# pi_shield_R4.net
KiCad netlist of a schematic drawn in EAGLE
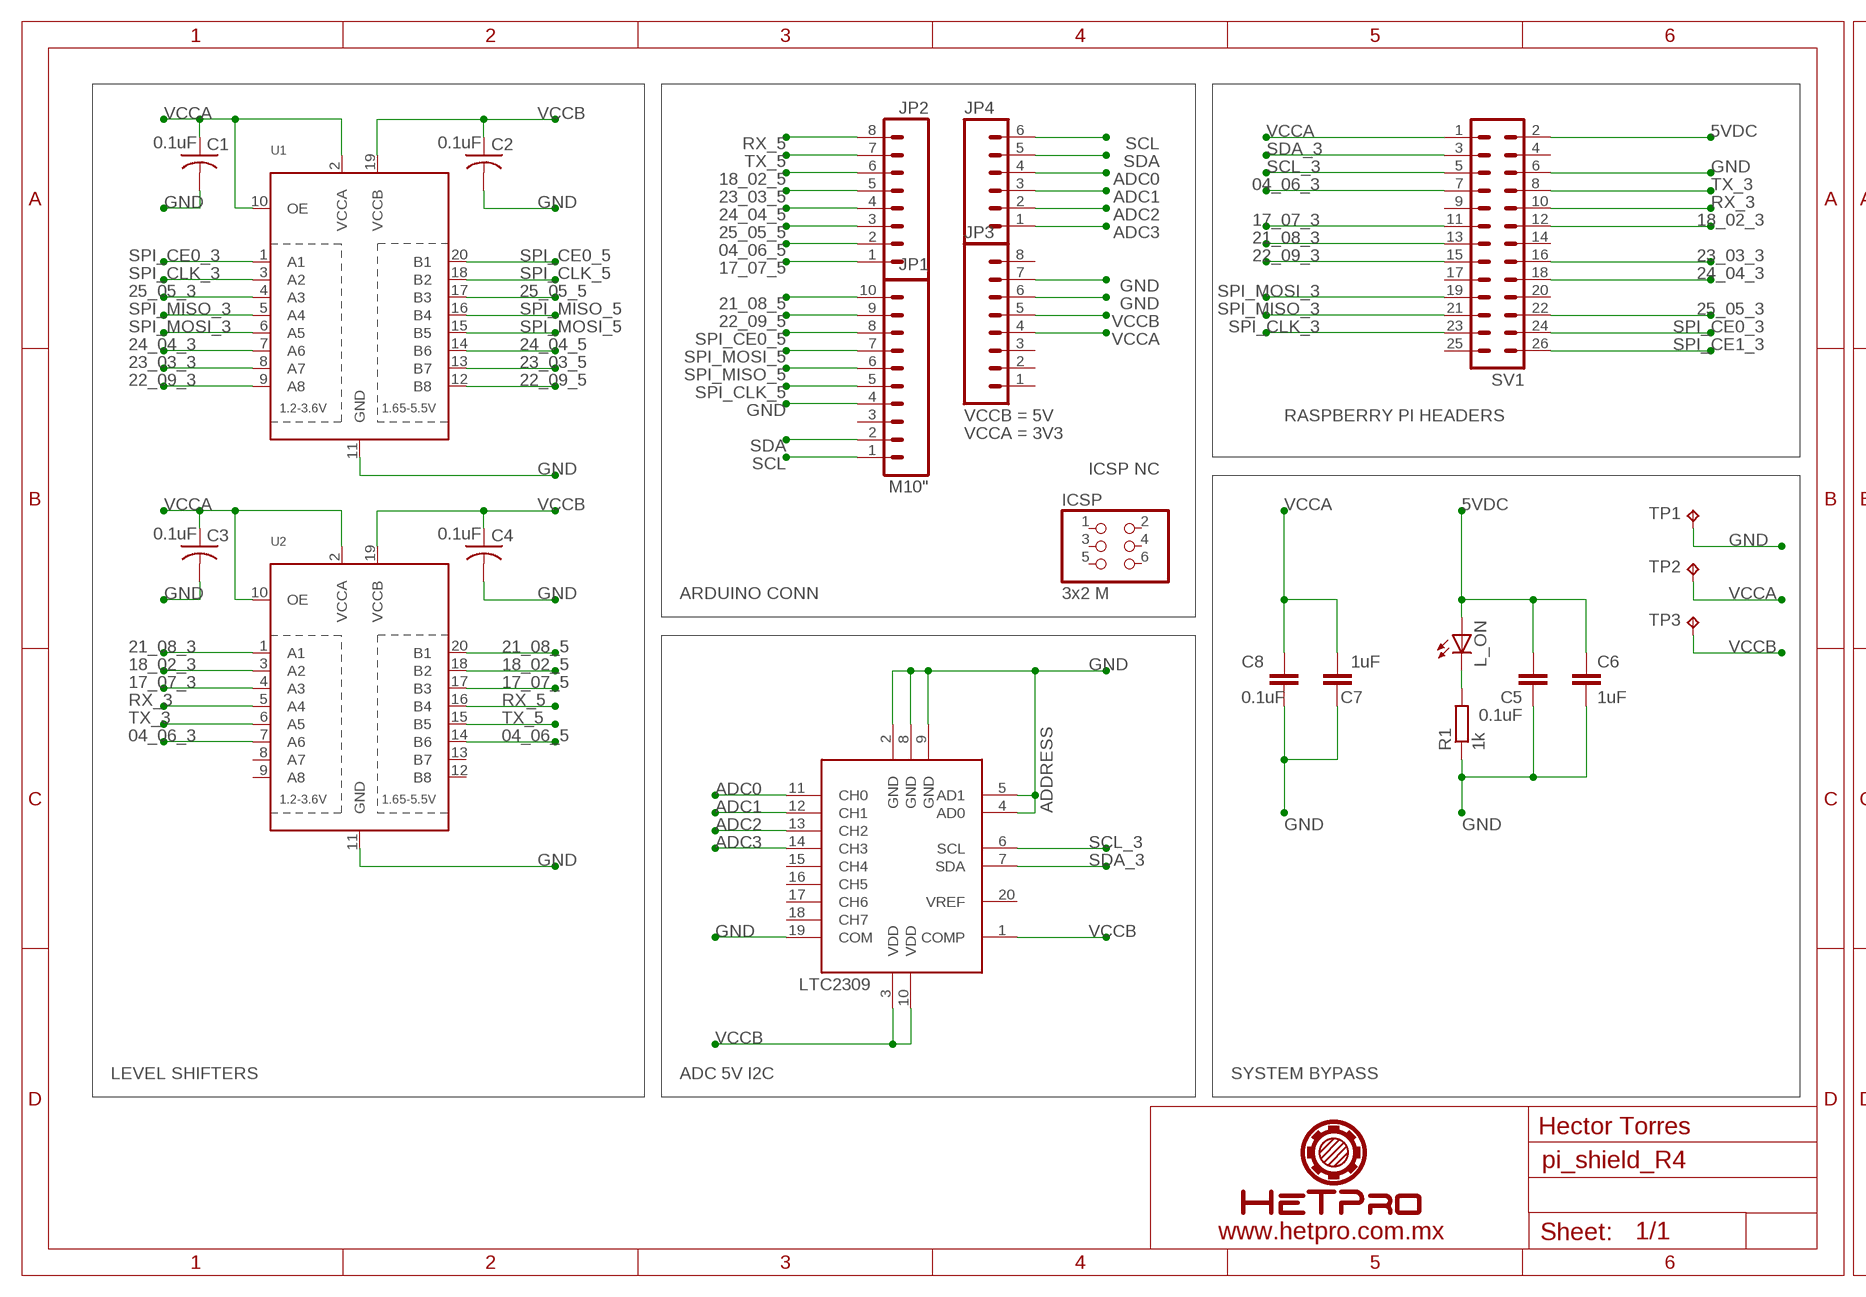
[diagram p0: schematic, sheet 1, part 1 of 2]
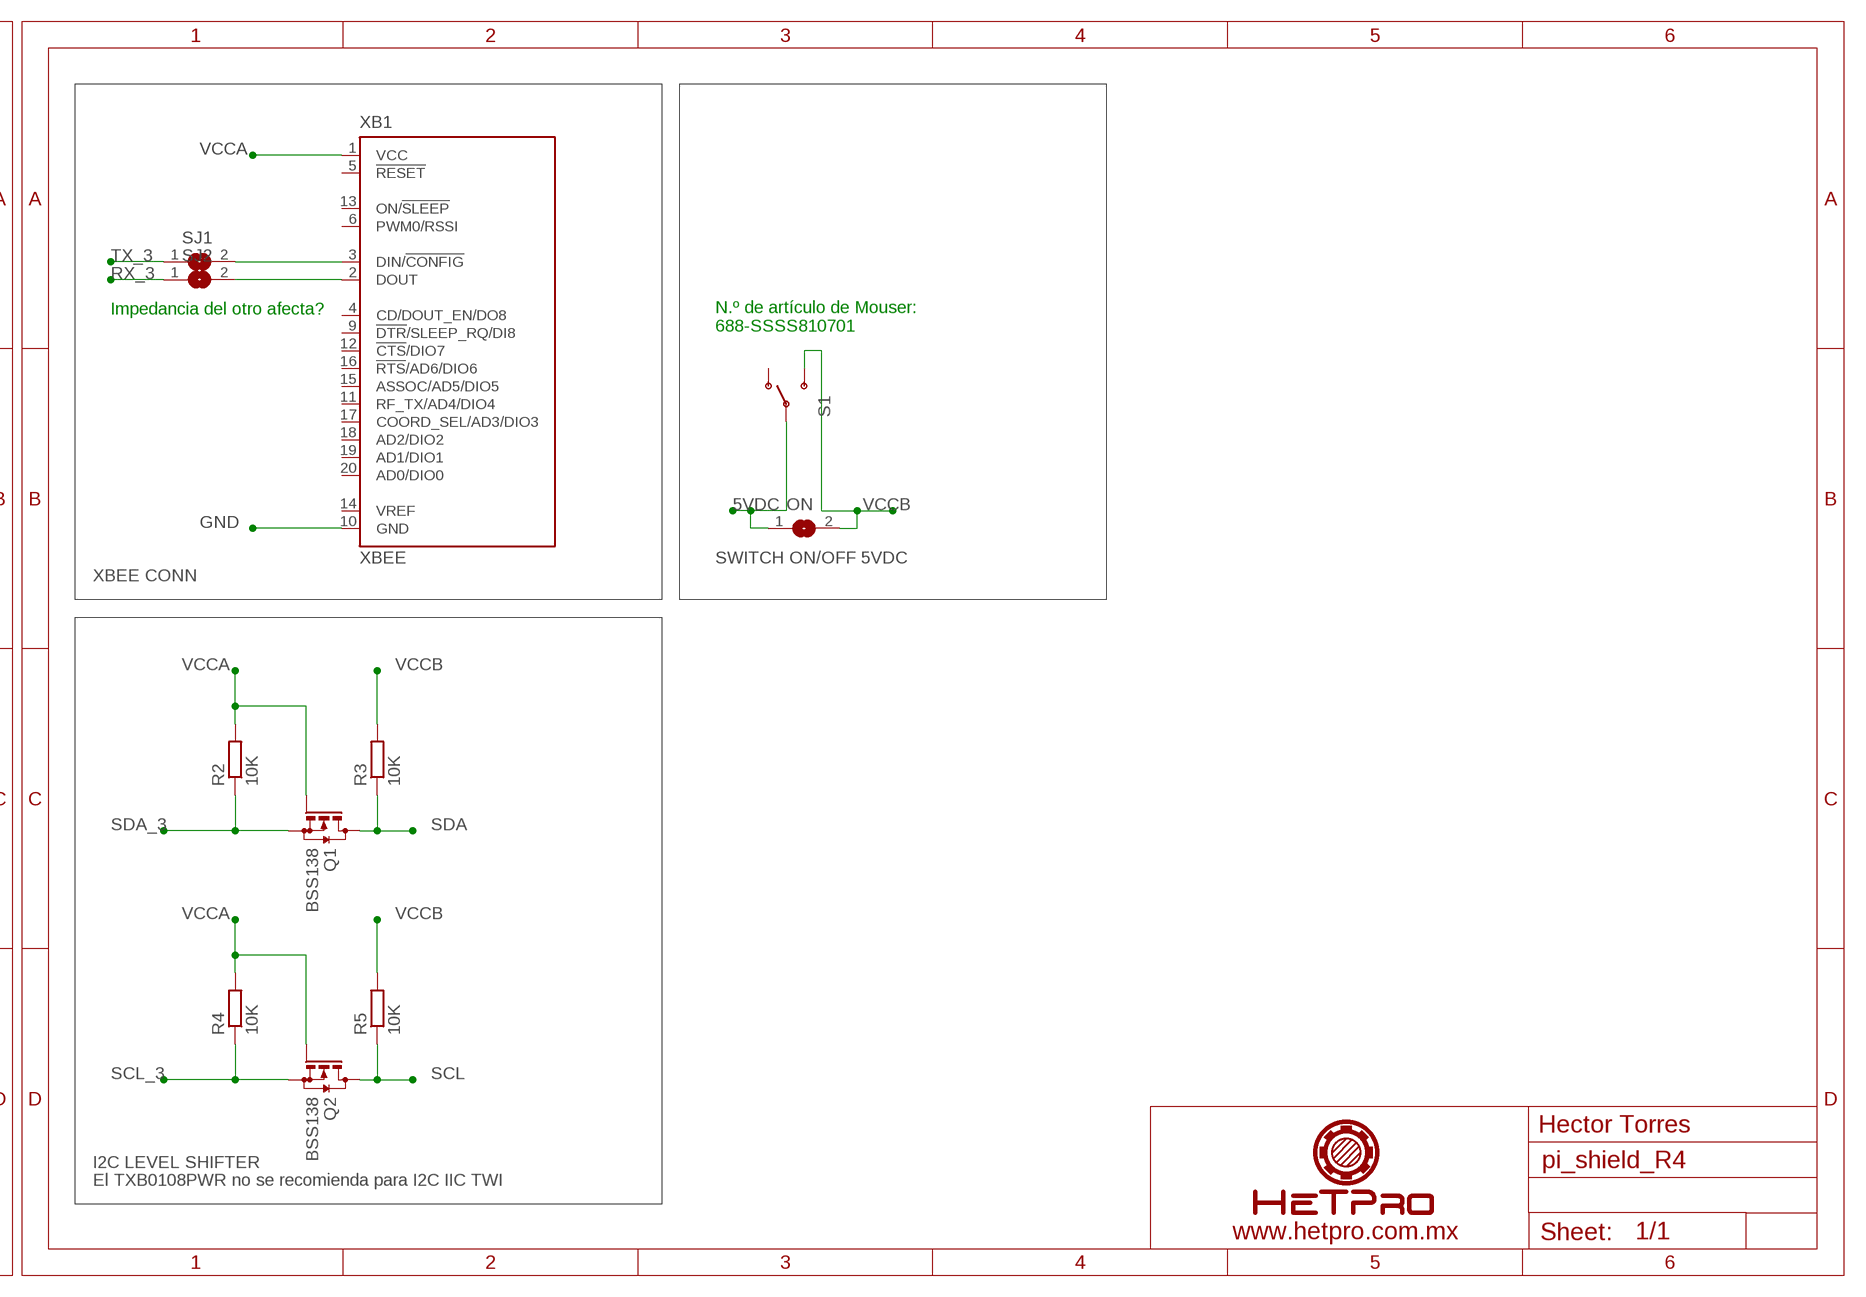
[diagram p1: schematic, sheet 1, part 2 of 2]

(export (version "E")
  (design (tool "Eeschema 10.0.6"))
  (components
    (comp (ref "C1")
      (value "0.1uF")
      (footprint "eagle-import:C0603")
      (libsource (lib "eagle-import") (part "C-USC0603"))
    )
    (comp (ref "C2")
      (value "0.1uF")
      (footprint "eagle-import:C0603")
      (libsource (lib "eagle-import") (part "C-USC0603"))
    )
    (comp (ref "C3")
      (value "0.1uF")
      (footprint "eagle-import:C0603")
      (libsource (lib "eagle-import") (part "C-USC0603"))
    )
    (comp (ref "C4")
      (value "0.1uF")
      (footprint "eagle-import:C0603")
      (libsource (lib "eagle-import") (part "C-USC0603"))
    )
    (comp (ref "C5")
      (value "0.1uF")
      (footprint "eagle-import:C0603")
      (libsource (lib "eagle-import") (part "C-EUC0603"))
    )
    (comp (ref "C6")
      (value "1uF")
      (footprint "eagle-import:C1206")
      (libsource (lib "eagle-import") (part "C-EUC1206"))
    )
    (comp (ref "C7")
      (value "1uF")
      (footprint "eagle-import:C0603")
      (libsource (lib "eagle-import") (part "C-EUC0603"))
    )
    (comp (ref "C8")
      (value "0.1uF")
      (footprint "eagle-import:C1206")
      (libsource (lib "eagle-import") (part "C-EUC1206"))
    )
    (comp (ref "ICSP")
      (value "3x2 M")
      (footprint "eagle-import:2X03")
      (libsource (lib "eagle-import") (part "PINHD-2X3"))
    )
    (comp (ref "JP1")
      (value "M10\"")
      (footprint "eagle-import:1X10")
      (libsource (lib "eagle-import") (part "M10{dblquote}"))
    )
    (comp (ref "JP2")
      (value "M081X08")
      (footprint "eagle-import:1X08")
      (libsource (lib "eagle-import") (part "M081X08"))
    )
    (comp (ref "JP3")
      (value "M081X08")
      (footprint "eagle-import:1X08")
      (libsource (lib "eagle-import") (part "M081X08"))
    )
    (comp (ref "JP4")
      (value "M06SIP")
      (footprint "eagle-import:1X06")
      (libsource (lib "eagle-import") (part "M06SIP"))
    )
    (comp (ref "L_ON")
      (value "LEDCHIPLED_1206")
      (footprint "eagle-import:CHIPLED_1206")
      (libsource (lib "eagle-import") (part "LEDCHIPLED_1206"))
    )
    (comp (ref "ON") (value "SJ") (footprint "eagle-import:SJ") (libsource (lib "eagle-import") (part "SJ")))
    (comp (ref "Q1")
      (value "BSS138")
      (footprint "eagle-import:SOT23")
      (libsource (lib "eagle-import") (part "BSS123"))
    )
    (comp (ref "Q2")
      (value "BSS138")
      (footprint "eagle-import:SOT23")
      (libsource (lib "eagle-import") (part "BSS123"))
    )
    (comp (ref "R1")
      (value "1k")
      (footprint "eagle-import:R0603")
      (libsource (lib "eagle-import") (part "R-EU_R0603"))
    )
    (comp (ref "R2")
      (value "10K")
      (footprint "eagle-import:R0603")
      (libsource (lib "eagle-import") (part "R-EU_R0603"))
    )
    (comp (ref "R3")
      (value "10K")
      (footprint "eagle-import:R0603")
      (libsource (lib "eagle-import") (part "R-EU_R0603"))
    )
    (comp (ref "R4")
      (value "10K")
      (footprint "eagle-import:R0603")
      (libsource (lib "eagle-import") (part "R-EU_R0603"))
    )
    (comp (ref "R5")
      (value "10K")
      (footprint "eagle-import:R0603")
      (libsource (lib "eagle-import") (part "R-EU_R0603"))
    )
    (comp (ref "S1")
      (value "SWITCH-SPST-SMD-A")
      (footprint "eagle-import:SWITCH-SPST-SMD-A")
      (libsource (lib "eagle-import") (part "SWITCH-SPST-SMD-A"))
    )
    (comp (ref "SJ1") (value "SJ") (footprint "eagle-import:SJ") (libsource (lib "eagle-import") (part "SJ")))
    (comp (ref "SJ2") (value "SJ") (footprint "eagle-import:SJ") (libsource (lib "eagle-import") (part "SJ")))
    (comp (ref "SV1")
      (value "MA13-2")
      (footprint "eagle-import:MA13-2")
      (fields (field (name "OC_FARNELL") "unknown") (field (name "OC_NEWARK") "unknown"))
      (libsource (lib "eagle-import") (part "MA13-2"))
    )
    (comp (ref "TP1")
      (value "TPTP20SQ")
      (footprint "eagle-import:TP20SQ")
      (libsource (lib "eagle-import") (part "TPTP20SQ"))
    )
    (comp (ref "TP2")
      (value "TPTP20SQ")
      (footprint "eagle-import:TP20SQ")
      (libsource (lib "eagle-import") (part "TPTP20SQ"))
    )
    (comp (ref "TP3")
      (value "TPTP20SQ")
      (footprint "eagle-import:TP20SQ")
      (libsource (lib "eagle-import") (part "TPTP20SQ"))
    )
    (comp (ref "U$4")
      (value "LTC2309")
      (footprint "eagle-import:TSSOP20")
      (libsource (lib "eagle-import") (part "LTC2309_TSSOP20"))
    )
    (comp (ref "U1")
      (value "TXB0108PWR")
      (footprint "eagle-import:TSSOP20")
      (libsource (lib "eagle-import") (part "TXB0108PWR"))
    )
    (comp (ref "U2")
      (value "TXB0108PWR")
      (footprint "eagle-import:TSSOP20")
      (libsource (lib "eagle-import") (part "TXB0108PWR"))
    )
    (comp (ref "XB1")
      (value "XBEE")
      (footprint "eagle-import:XBEE")
      (fields (field (name "MPN") "XBP24-Z7UIT-004"))
      (libsource (lib "eagle-import") (part "XBEE"))
    )
  )
  (nets
    (net (code "1") (name "/04_06_3") (class "Default")
      (node (ref "SV1") (pin "7") (pinfunction "7_7") (pintype "passive"))
      (node (ref "U2") (pin "7") (pinfunction "A6_7") (pintype "bidirectional"))
    )
    (net (code "2") (name "/04_06_5") (class "Default")
      (node (ref "JP2") (pin "2") (pinfunction "2_2") (pintype "passive"))
      (node (ref "U2") (pin "14") (pinfunction "B6_14") (pintype "bidirectional"))
    )
    (net (code "3") (name "/5VDC") (class "Default")
      (node (ref "C5") (pin "2") (pinfunction "2_2") (pintype "passive"))
      (node (ref "C6") (pin "1") (pinfunction "1_1") (pintype "passive"))
      (node (ref "L_ON") (pin "A") (pinfunction "A_A") (pintype "passive"))
      (node (ref "ON") (pin "1") (pinfunction "1_1") (pintype "passive"))
      (node (ref "S1") (pin "2") (pinfunction "P_2") (pintype "passive"))
      (node (ref "SV1") (pin "2") (pinfunction "2_2") (pintype "passive"))
    )
    (net (code "4") (name "/17_07_3") (class "Default")
      (node (ref "SV1") (pin "11") (pinfunction "11_11") (pintype "passive"))
      (node (ref "U2") (pin "4") (pinfunction "A3_4") (pintype "bidirectional"))
    )
    (net (code "5") (name "/17_07_5") (class "Default")
      (node (ref "JP2") (pin "1") (pinfunction "1_1") (pintype "passive"))
      (node (ref "U2") (pin "17") (pinfunction "B3_17") (pintype "bidirectional"))
    )
    (net (code "6") (name "/18_02_3") (class "Default")
      (node (ref "SV1") (pin "12") (pinfunction "12_12") (pintype "passive"))
      (node (ref "U2") (pin "3") (pinfunction "A2_3") (pintype "bidirectional"))
    )
    (net (code "7") (name "/18_02_5") (class "Default")
      (node (ref "JP2") (pin "6") (pinfunction "6_6") (pintype "passive"))
      (node (ref "U2") (pin "18") (pinfunction "B2_18") (pintype "bidirectional"))
    )
    (net (code "8") (name "/21_08_3") (class "Default")
      (node (ref "SV1") (pin "13") (pinfunction "13_13") (pintype "passive"))
      (node (ref "U2") (pin "1") (pinfunction "A1_1") (pintype "bidirectional"))
    )
    (net (code "9") (name "/21_08_5") (class "Default")
      (node (ref "JP1") (pin "10") (pinfunction "10_10") (pintype "passive"))
      (node (ref "U2") (pin "20") (pinfunction "B1_20") (pintype "bidirectional"))
    )
    (net (code "10") (name "/22_09_3") (class "Default")
      (node (ref "SV1") (pin "15") (pinfunction "15_15") (pintype "passive"))
      (node (ref "U1") (pin "9") (pinfunction "A8_9") (pintype "bidirectional"))
    )
    (net (code "11") (name "/22_09_5") (class "Default")
      (node (ref "JP1") (pin "9") (pinfunction "9_9") (pintype "passive"))
      (node (ref "U1") (pin "12") (pinfunction "B8_12") (pintype "bidirectional"))
    )
    (net (code "12") (name "/23_03_3") (class "Default")
      (node (ref "SV1") (pin "16") (pinfunction "16_16") (pintype "passive"))
      (node (ref "U1") (pin "8") (pinfunction "A7_8") (pintype "bidirectional"))
    )
    (net (code "13") (name "/23_03_5") (class "Default")
      (node (ref "JP2") (pin "5") (pinfunction "5_5") (pintype "passive"))
      (node (ref "U1") (pin "13") (pinfunction "B7_13") (pintype "bidirectional"))
    )
    (net (code "14") (name "/24_04_3") (class "Default")
      (node (ref "SV1") (pin "18") (pinfunction "18_18") (pintype "passive"))
      (node (ref "U1") (pin "7") (pinfunction "A6_7") (pintype "bidirectional"))
    )
    (net (code "15") (name "/24_04_5") (class "Default")
      (node (ref "JP2") (pin "4") (pinfunction "4_4") (pintype "passive"))
      (node (ref "U1") (pin "14") (pinfunction "B6_14") (pintype "bidirectional"))
    )
    (net (code "16") (name "/25_05_3") (class "Default")
      (node (ref "SV1") (pin "22") (pinfunction "22_22") (pintype "passive"))
      (node (ref "U1") (pin "4") (pinfunction "A3_4") (pintype "bidirectional"))
    )
    (net (code "17") (name "/25_05_5") (class "Default")
      (node (ref "JP2") (pin "3") (pinfunction "3_3") (pintype "passive"))
      (node (ref "U1") (pin "17") (pinfunction "B3_17") (pintype "bidirectional"))
    )
    (net (code "18") (name "/ADC0") (class "Default")
      (node (ref "JP4") (pin "4") (pinfunction "4_4") (pintype "passive"))
      (node (ref "U$4") (pin "11") (pinfunction "CH0_11") (pintype "bidirectional"))
    )
    (net (code "19") (name "/ADC1") (class "Default")
      (node (ref "JP4") (pin "3") (pinfunction "3_3") (pintype "passive"))
      (node (ref "U$4") (pin "12") (pinfunction "CH1_12") (pintype "bidirectional"))
    )
    (net (code "20") (name "/ADC2") (class "Default")
      (node (ref "JP4") (pin "2") (pinfunction "2_2") (pintype "passive"))
      (node (ref "U$4") (pin "13") (pinfunction "CH2_13") (pintype "bidirectional"))
    )
    (net (code "21") (name "/ADC3") (class "Default")
      (node (ref "JP4") (pin "1") (pinfunction "1_1") (pintype "passive"))
      (node (ref "U$4") (pin "14") (pinfunction "CH3_14") (pintype "bidirectional"))
    )
    (net (code "22") (name "/GND") (class "Default")
      (node (ref "C1") (pin "2") (pinfunction "2_2") (pintype "passive"))
      (node (ref "C2") (pin "2") (pinfunction "2_2") (pintype "passive"))
      (node (ref "C3") (pin "2") (pinfunction "2_2") (pintype "passive"))
      (node (ref "C4") (pin "2") (pinfunction "2_2") (pintype "passive"))
      (node (ref "C5") (pin "1") (pinfunction "1_1") (pintype "passive"))
      (node (ref "C6") (pin "2") (pinfunction "2_2") (pintype "passive"))
      (node (ref "C7") (pin "1") (pinfunction "1_1") (pintype "passive"))
      (node (ref "C8") (pin "2") (pinfunction "2_2") (pintype "passive"))
      (node (ref "JP1") (pin "4") (pinfunction "4_4") (pintype "passive"))
      (node (ref "JP3") (pin "6") (pinfunction "6_6") (pintype "passive"))
      (node (ref "JP3") (pin "7") (pinfunction "7_7") (pintype "passive"))
      (node (ref "R1") (pin "1") (pinfunction "1_1") (pintype "passive"))
      (node (ref "SV1") (pin "6") (pinfunction "6_6") (pintype "passive"))
      (node (ref "TP1") (pin "TP") (pinfunction "TP_TP") (pintype "input"))
      (node (ref "U$4") (pin "19") (pinfunction "COM_19") (pintype "bidirectional"))
      (node (ref "U$4") (pin "2") (pinfunction "GND_2") (pintype "bidirectional"))
      (node (ref "U$4") (pin "4") (pinfunction "AD0_4") (pintype "bidirectional"))
      (node (ref "U$4") (pin "5") (pinfunction "AD1_5") (pintype "bidirectional"))
      (node (ref "U$4") (pin "8") (pinfunction "GND_8") (pintype "bidirectional"))
      (node (ref "U$4") (pin "9") (pinfunction "GND_9") (pintype "bidirectional"))
      (node (ref "U1") (pin "11") (pinfunction "GND_11") (pintype "bidirectional"))
      (node (ref "U2") (pin "11") (pinfunction "GND_11") (pintype "bidirectional"))
      (node (ref "XB1") (pin "10") (pinfunction "GND_10") (pintype "power_in"))
    )
    (net (code "23") (name "/RX_3") (class "Default")
      (node (ref "SJ2") (pin "1") (pinfunction "1_1") (pintype "passive"))
      (node (ref "SV1") (pin "10") (pinfunction "10_10") (pintype "passive"))
      (node (ref "U2") (pin "5") (pinfunction "A4_5") (pintype "bidirectional"))
    )
    (net (code "24") (name "/RX_5") (class "Default")
      (node (ref "JP2") (pin "8") (pinfunction "8_8") (pintype "passive"))
      (node (ref "U2") (pin "16") (pinfunction "B4_16") (pintype "bidirectional"))
    )
    (net (code "25") (name "/SCL") (class "Default")
      (node (ref "JP1") (pin "1") (pinfunction "1_1") (pintype "passive"))
      (node (ref "JP4") (pin "6") (pinfunction "6_6") (pintype "passive"))
      (node (ref "Q2") (pin "3") (pinfunction "D_3") (pintype "passive"))
      (node (ref "R5") (pin "1") (pinfunction "1_1") (pintype "passive"))
    )
    (net (code "26") (name "/SCL_3") (class "Default")
      (node (ref "Q2") (pin "2") (pinfunction "S_2") (pintype "passive"))
      (node (ref "R4") (pin "1") (pinfunction "1_1") (pintype "passive"))
      (node (ref "SV1") (pin "5") (pinfunction "5_5") (pintype "passive"))
      (node (ref "U$4") (pin "6") (pinfunction "SCL_6") (pintype "bidirectional"))
    )
    (net (code "27") (name "/SDA") (class "Default")
      (node (ref "JP1") (pin "2") (pinfunction "2_2") (pintype "passive"))
      (node (ref "JP4") (pin "5") (pinfunction "5_5") (pintype "passive"))
      (node (ref "Q1") (pin "3") (pinfunction "D_3") (pintype "passive"))
      (node (ref "R3") (pin "1") (pinfunction "1_1") (pintype "passive"))
    )
    (net (code "28") (name "/SDA_3") (class "Default")
      (node (ref "Q1") (pin "2") (pinfunction "S_2") (pintype "passive"))
      (node (ref "R2") (pin "1") (pinfunction "1_1") (pintype "passive"))
      (node (ref "SV1") (pin "3") (pinfunction "3_3") (pintype "passive"))
      (node (ref "U$4") (pin "7") (pinfunction "SDA_7") (pintype "bidirectional"))
    )
    (net (code "29") (name "/SPI_CE0_3") (class "Default")
      (node (ref "SV1") (pin "24") (pinfunction "24_24") (pintype "passive"))
      (node (ref "U1") (pin "1") (pinfunction "A1_1") (pintype "bidirectional"))
    )
    (net (code "30") (name "/SPI_CE0_5") (class "Default")
      (node (ref "JP1") (pin "8") (pinfunction "8_8") (pintype "passive"))
      (node (ref "U1") (pin "20") (pinfunction "B1_20") (pintype "bidirectional"))
    )
    (net (code "31") (name "/SPI_CE1_3") (class "Default")
      (node (ref "SV1") (pin "26") (pinfunction "26_26") (pintype "passive"))
    )
    (net (code "32") (name "/SPI_CLK_3") (class "Default")
      (node (ref "SV1") (pin "23") (pinfunction "23_23") (pintype "passive"))
      (node (ref "U1") (pin "3") (pinfunction "A2_3") (pintype "bidirectional"))
    )
    (net (code "33") (name "/SPI_CLK_5") (class "Default")
      (node (ref "JP1") (pin "5") (pinfunction "5_5") (pintype "passive"))
      (node (ref "U1") (pin "18") (pinfunction "B2_18") (pintype "bidirectional"))
    )
    (net (code "34") (name "/SPI_MISO_3") (class "Default")
      (node (ref "SV1") (pin "21") (pinfunction "21_21") (pintype "passive"))
      (node (ref "U1") (pin "5") (pinfunction "A4_5") (pintype "bidirectional"))
    )
    (net (code "35") (name "/SPI_MISO_5") (class "Default")
      (node (ref "JP1") (pin "6") (pinfunction "6_6") (pintype "passive"))
      (node (ref "U1") (pin "16") (pinfunction "B4_16") (pintype "bidirectional"))
    )
    (net (code "36") (name "/SPI_MOSI_3") (class "Default")
      (node (ref "SV1") (pin "19") (pinfunction "19_19") (pintype "passive"))
      (node (ref "U1") (pin "6") (pinfunction "A5_6") (pintype "bidirectional"))
    )
    (net (code "37") (name "/SPI_MOSI_5") (class "Default")
      (node (ref "JP1") (pin "7") (pinfunction "7_7") (pintype "passive"))
      (node (ref "U1") (pin "15") (pinfunction "B5_15") (pintype "bidirectional"))
    )
    (net (code "38") (name "/TX_3") (class "Default")
      (node (ref "SJ1") (pin "1") (pinfunction "1_1") (pintype "passive"))
      (node (ref "SV1") (pin "8") (pinfunction "8_8") (pintype "passive"))
      (node (ref "U2") (pin "6") (pinfunction "A5_6") (pintype "bidirectional"))
    )
    (net (code "39") (name "/TX_5") (class "Default")
      (node (ref "JP2") (pin "7") (pinfunction "7_7") (pintype "passive"))
      (node (ref "U2") (pin "15") (pinfunction "B5_15") (pintype "bidirectional"))
    )
    (net (code "40") (name "/VCCA") (class "Default")
      (node (ref "C1") (pin "1") (pinfunction "1_1") (pintype "passive"))
      (node (ref "C3") (pin "1") (pinfunction "1_1") (pintype "passive"))
      (node (ref "C7") (pin "2") (pinfunction "2_2") (pintype "passive"))
      (node (ref "C8") (pin "1") (pinfunction "1_1") (pintype "passive"))
      (node (ref "JP3") (pin "4") (pinfunction "4_4") (pintype "passive"))
      (node (ref "Q1") (pin "1") (pinfunction "G_1") (pintype "passive"))
      (node (ref "Q2") (pin "1") (pinfunction "G_1") (pintype "passive"))
      (node (ref "R2") (pin "2") (pinfunction "2_2") (pintype "passive"))
      (node (ref "R4") (pin "2") (pinfunction "2_2") (pintype "passive"))
      (node (ref "SV1") (pin "1") (pinfunction "1_1") (pintype "passive"))
      (node (ref "TP2") (pin "TP") (pinfunction "TP_TP") (pintype "input"))
      (node (ref "U1") (pin "10") (pinfunction "OE_10") (pintype "bidirectional"))
      (node (ref "U1") (pin "2") (pinfunction "VCCA_2") (pintype "bidirectional"))
      (node (ref "U2") (pin "10") (pinfunction "OE_10") (pintype "bidirectional"))
      (node (ref "U2") (pin "2") (pinfunction "VCCA_2") (pintype "bidirectional"))
      (node (ref "XB1") (pin "1") (pinfunction "VCC_1") (pintype "power_in"))
    )
    (net (code "41") (name "/VCCB") (class "Default")
      (node (ref "C2") (pin "1") (pinfunction "1_1") (pintype "passive"))
      (node (ref "C4") (pin "1") (pinfunction "1_1") (pintype "passive"))
      (node (ref "JP3") (pin "5") (pinfunction "5_5") (pintype "passive"))
      (node (ref "ON") (pin "2") (pinfunction "2_2") (pintype "passive"))
      (node (ref "R3") (pin "2") (pinfunction "2_2") (pintype "passive"))
      (node (ref "R5") (pin "2") (pinfunction "2_2") (pintype "passive"))
      (node (ref "S1") (pin "3") (pinfunction "S_3") (pintype "passive"))
      (node (ref "TP3") (pin "TP") (pinfunction "TP_TP") (pintype "input"))
      (node (ref "U$4") (pin "1") (pinfunction "COMP_1") (pintype "bidirectional"))
      (node (ref "U$4") (pin "10") (pinfunction "VDD_10") (pintype "bidirectional"))
      (node (ref "U$4") (pin "3") (pinfunction "VDD_3") (pintype "bidirectional"))
      (node (ref "U1") (pin "19") (pinfunction "VCCB_19") (pintype "bidirectional"))
      (node (ref "U2") (pin "19") (pinfunction "VCCB_19") (pintype "bidirectional"))
    )
    (net (code "42") (name "Net-(L_ON-PadC)") (class "Default")
      (node (ref "L_ON") (pin "C") (pinfunction "C_C") (pintype "passive"))
      (node (ref "R1") (pin "2") (pinfunction "2_2") (pintype "passive"))
    )
    (net (code "43") (name "Net-(XB1-DIN{slash}~{CONFIG})") (class "Default")
      (node (ref "SJ1") (pin "2") (pinfunction "2_2") (pintype "passive"))
      (node (ref "XB1") (pin "3") (pinfunction "DIN/~{CONFIG}_3") (pintype "input"))
    )
    (net (code "44") (name "Net-(XB1-DOUT)") (class "Default")
      (node (ref "SJ2") (pin "2") (pinfunction "2_2") (pintype "passive"))
      (node (ref "XB1") (pin "2") (pinfunction "DOUT_2") (pintype "output"))
    )
    (net (code "45") (name "unconnected-(ICSP-Pad1)") (class "Default")
      (node (ref "ICSP") (pin "1") (pinfunction "1_1") (pintype "passive"))
    )
    (net (code "46") (name "unconnected-(ICSP-Pad2)") (class "Default")
      (node (ref "ICSP") (pin "2") (pinfunction "2_2") (pintype "passive"))
    )
    (net (code "47") (name "unconnected-(ICSP-Pad3)") (class "Default")
      (node (ref "ICSP") (pin "3") (pinfunction "3_3") (pintype "passive"))
    )
    (net (code "48") (name "unconnected-(ICSP-Pad4)") (class "Default")
      (node (ref "ICSP") (pin "4") (pinfunction "4_4") (pintype "passive"))
    )
    (net (code "49") (name "unconnected-(ICSP-Pad5)") (class "Default")
      (node (ref "ICSP") (pin "5") (pinfunction "5_5") (pintype "passive"))
    )
    (net (code "50") (name "unconnected-(ICSP-Pad6)") (class "Default")
      (node (ref "ICSP") (pin "6") (pinfunction "6_6") (pintype "passive"))
    )
    (net (code "51") (name "unconnected-(JP1-Pad3)") (class "Default")
      (node (ref "JP1") (pin "3") (pinfunction "3_3") (pintype "passive"))
    )
    (net (code "52") (name "unconnected-(JP3-Pad1)") (class "Default")
      (node (ref "JP3") (pin "1") (pinfunction "1_1") (pintype "passive"))
    )
    (net (code "53") (name "unconnected-(JP3-Pad2)") (class "Default")
      (node (ref "JP3") (pin "2") (pinfunction "2_2") (pintype "passive"))
    )
    (net (code "54") (name "unconnected-(JP3-Pad3)") (class "Default")
      (node (ref "JP3") (pin "3") (pinfunction "3_3") (pintype "passive"))
    )
    (net (code "55") (name "unconnected-(JP3-Pad8)") (class "Default")
      (node (ref "JP3") (pin "8") (pinfunction "8_8") (pintype "passive"))
    )
    (net (code "56") (name "unconnected-(S1-O-Pad1)") (class "Default")
      (node (ref "S1") (pin "1") (pinfunction "O_1") (pintype "passive"))
    )
    (net (code "57") (name "unconnected-(SV1-Pad4)") (class "Default")
      (node (ref "SV1") (pin "4") (pinfunction "4_4") (pintype "passive"))
    )
    (net (code "58") (name "unconnected-(SV1-Pad9)") (class "Default")
      (node (ref "SV1") (pin "9") (pinfunction "9_9") (pintype "passive"))
    )
    (net (code "59") (name "unconnected-(SV1-Pad14)") (class "Default")
      (node (ref "SV1") (pin "14") (pinfunction "14_14") (pintype "passive"))
    )
    (net (code "60") (name "unconnected-(SV1-Pad17)") (class "Default")
      (node (ref "SV1") (pin "17") (pinfunction "17_17") (pintype "passive"))
    )
    (net (code "61") (name "unconnected-(SV1-Pad20)") (class "Default")
      (node (ref "SV1") (pin "20") (pinfunction "20_20") (pintype "passive"))
    )
    (net (code "62") (name "unconnected-(SV1-Pad25)") (class "Default")
      (node (ref "SV1") (pin "25") (pinfunction "25_25") (pintype "passive"))
    )
    (net (code "63") (name "unconnected-(U$4-CH4-Pad15)") (class "Default")
      (node (ref "U$4") (pin "15") (pinfunction "CH4_15") (pintype "bidirectional"))
    )
    (net (code "64") (name "unconnected-(U$4-CH5-Pad16)") (class "Default")
      (node (ref "U$4") (pin "16") (pinfunction "CH5_16") (pintype "bidirectional"))
    )
    (net (code "65") (name "unconnected-(U$4-CH6-Pad17)") (class "Default")
      (node (ref "U$4") (pin "17") (pinfunction "CH6_17") (pintype "bidirectional"))
    )
    (net (code "66") (name "unconnected-(U$4-CH7-Pad18)") (class "Default")
      (node (ref "U$4") (pin "18") (pinfunction "CH7_18") (pintype "bidirectional"))
    )
    (net (code "67") (name "unconnected-(U$4-VREF-Pad20)") (class "Default")
      (node (ref "U$4") (pin "20") (pinfunction "VREF_20") (pintype "bidirectional"))
    )
    (net (code "68") (name "unconnected-(U2-A7-Pad8)") (class "Default")
      (node (ref "U2") (pin "8") (pinfunction "A7_8") (pintype "bidirectional"))
    )
    (net (code "69") (name "unconnected-(U2-A8-Pad9)") (class "Default")
      (node (ref "U2") (pin "9") (pinfunction "A8_9") (pintype "bidirectional"))
    )
    (net (code "70") (name "unconnected-(U2-B7-Pad13)") (class "Default")
      (node (ref "U2") (pin "13") (pinfunction "B7_13") (pintype "bidirectional"))
    )
    (net (code "71") (name "unconnected-(U2-B8-Pad12)") (class "Default")
      (node (ref "U2") (pin "12") (pinfunction "B8_12") (pintype "bidirectional"))
    )
    (net (code "72") (name "unconnected-(XB1-AD0{slash}DIO0-Pad20)") (class "Default")
      (node (ref "XB1") (pin "20") (pinfunction "AD0/DIO0_20") (pintype "bidirectional"))
    )
    (net (code "73") (name "unconnected-(XB1-AD1{slash}DIO1-Pad19)") (class "Default")
      (node (ref "XB1") (pin "19") (pinfunction "AD1/DIO1_19") (pintype "bidirectional"))
    )
    (net (code "74") (name "unconnected-(XB1-AD2{slash}DIO2-Pad18)") (class "Default")
      (node (ref "XB1") (pin "18") (pinfunction "AD2/DIO2_18") (pintype "bidirectional"))
    )
    (net (code "75") (name "unconnected-(XB1-ASSOC{slash}AD5{slash}DIO5-Pad15)") (class "Default")
      (node (ref "XB1") (pin "15") (pinfunction "ASSOC/AD5/DIO5_15") (pintype "bidirectional"))
    )
    (net (code "76") (name "unconnected-(XB1-CD{slash}DOUT_EN{slash}DO8-Pad4)") (class "Default")
      (node (ref "XB1") (pin "4") (pinfunction "CD/DOUT_EN/DO8_4") (pintype "output"))
    )
    (net (code "77") (name "unconnected-(XB1-COORD_SEL{slash}AD3{slash}DIO3-Pad17)") (class "Default")
      (node (ref "XB1") (pin "17") (pinfunction "COORD_SEL/AD3/DIO3_17") (pintype "bidirectional"))
    )
    (net (code "78") (name "unconnected-(XB1-ON{slash}~{SLEEP}-Pad13)") (class "Default")
      (node (ref "XB1") (pin "13") (pinfunction "ON/~{SLEEP}_13") (pintype "output"))
    )
    (net (code "79") (name "unconnected-(XB1-PWM0{slash}RSSI-Pad6)") (class "Default")
      (node (ref "XB1") (pin "6") (pinfunction "PWM0/RSSI_6") (pintype "output"))
    )
    (net (code "80") (name "unconnected-(XB1-RF_TX{slash}AD4{slash}DIO4-Pad11)") (class "Default")
      (node (ref "XB1") (pin "11") (pinfunction "RF_TX/AD4/DIO4_11") (pintype "bidirectional"))
    )
    (net (code "81") (name "unconnected-(XB1-VREF-Pad14)") (class "Default")
      (node (ref "XB1") (pin "14") (pinfunction "VREF_14") (pintype "input"))
    )
    (net (code "82") (name "unconnected-(XB1-~{CTS}{slash}DIO7-Pad12)") (class "Default")
      (node (ref "XB1") (pin "12") (pinfunction "~{CTS}/DIO7_12") (pintype "bidirectional"))
    )
    (net (code "83") (name "unconnected-(XB1-~{DTR}{slash}SLEEP_RQ{slash}DI8-Pad9)") (class "Default")
      (node (ref "XB1") (pin "9") (pinfunction "~{DTR}/SLEEP_RQ/DI8_9") (pintype "bidirectional"))
    )
    (net (code "84") (name "unconnected-(XB1-~{RESET}-Pad5)") (class "Default")
      (node (ref "XB1") (pin "5") (pinfunction "~{RESET}_5") (pintype "input"))
    )
    (net (code "85") (name "unconnected-(XB1-~{RTS}{slash}AD6{slash}DIO6-Pad16)") (class "Default")
      (node (ref "XB1") (pin "16") (pinfunction "~{RTS}/AD6/DIO6_16") (pintype "bidirectional"))
    )
  )
)
